# Sheet3.net
KiCad netlist of a schematic drawn in Altium Designer
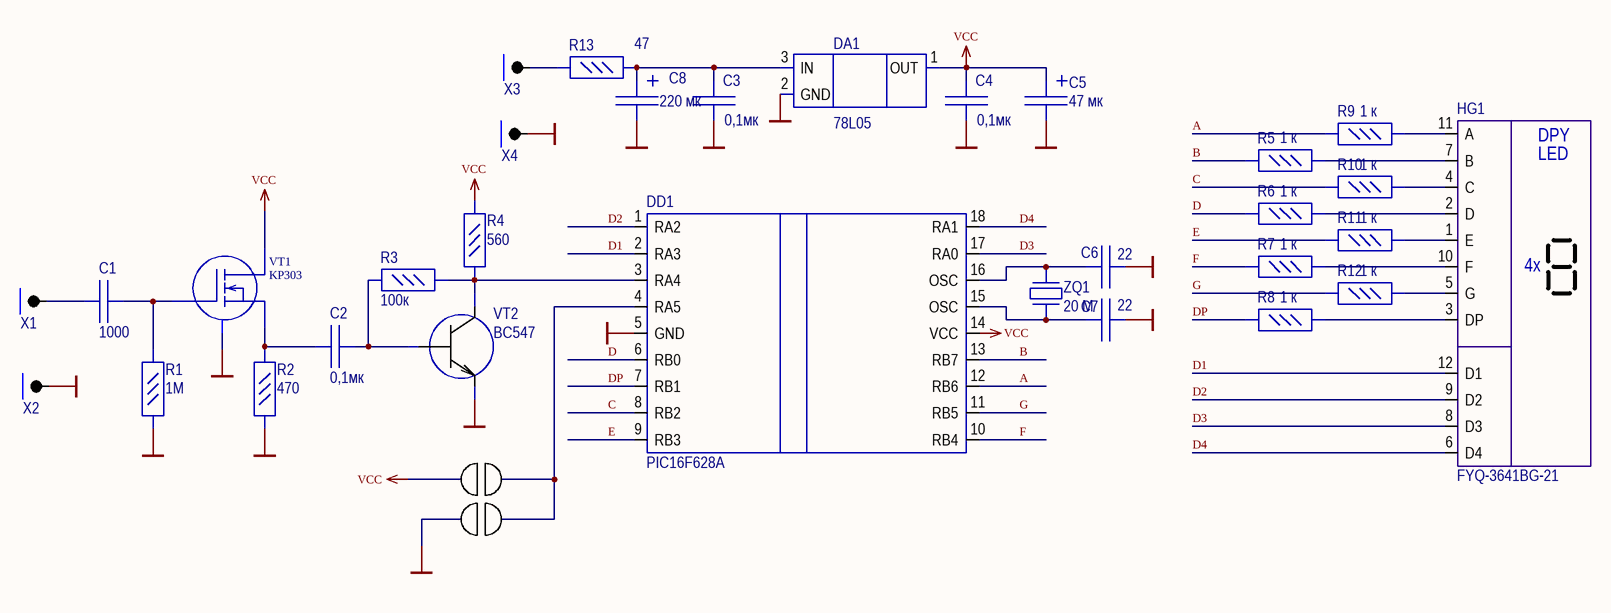
[diagram p0: Sheet3.SchDoc]

(export (version "E")
  (design (tool "Eeschema 10.0.6"))
  (components
    (comp (ref "C1") (value "1000") (footprint "К10-17Б") (libsource (lib "1. Passive") (part "C_К10-17Б")))
    (comp (ref "C2") (value "0,1мк") (footprint "К10-17Б") (libsource (lib "1. Passive") (part "C_К10-17Б")))
    (comp (ref "C3") (value "0,1мк") (footprint "К10-17Б") (libsource (lib "1. Passive") (part "C_К10-17Б")))
    (comp (ref "C4") (value "0,1мк") (footprint "К10-17Б") (libsource (lib "1. Passive") (part "C_К10-17Б")))
    (comp (ref "C5") (value "47 мк") (footprint "К50-35") (libsource (lib "1. Passive") (part "K50-35")))
    (comp (ref "C6") (value "22") (footprint "К10-17Б") (libsource (lib "1. Passive") (part "C_К10-17Б")))
    (comp (ref "C7") (value "22") (footprint "К10-17Б") (libsource (lib "1. Passive") (part "C_К10-17Б")))
    (comp (ref "C8")
      (value "220 мк")
      (footprint "К50-35 - 8x11.5")
      (libsource (lib "1. Passive") (part "K50-35"))
    )
    (comp (ref "DA1") (value "78L05") (footprint "КТ-26") (libsource (lib "2. Chips") (part "78L06")))
    (comp (ref "DD1")
      (value "PIC16F628A")
      (footprint "DIP18")
      (fields
        (field (name "MANUFACTURER PART NUMBER") "TB6600HG(O)")
        (field (name "OCTOPART") "https://octopart.com/tb6600hg%28o%29-toshiba-24612481")
        (field (name "MANUFACTURER") "Toshiba")
      )
      (libsource (lib "2. Chips") (part "PIC16F628A"))
    )
    (comp (ref "HG1")
      (value "FYQ-3641BG-21")
      (footprint "FYQ-3641")
      (description "4-х разр. светод. индикатор, зеленый, (ОА)")
      (libsource (lib "8. Other") (part "FYQ-3641BG-21"))
    )
    (comp (ref "R1") (value "1М") (footprint "R_C1-4_V") (libsource (lib "1. Passive") (part "R_C1-4")))
    (comp (ref "R2") (value "470") (footprint "R_C1-4_V") (libsource (lib "1. Passive") (part "R_C1-4")))
    (comp (ref "R3") (value "100к") (footprint "R_C1-4_V") (libsource (lib "1. Passive") (part "R_C1-4")))
    (comp (ref "R4") (value "560") (footprint "R_C1-4_V") (libsource (lib "1. Passive") (part "R_C1-4")))
    (comp (ref "R5") (value "1 к") (footprint "R_C1-4_V") (libsource (lib "1. Passive") (part "R_C1-4")))
    (comp (ref "R6") (value "1 к") (footprint "R_C1-4_V") (libsource (lib "1. Passive") (part "R_C1-4")))
    (comp (ref "R7") (value "1 к") (footprint "R_C1-4_V") (libsource (lib "1. Passive") (part "R_C1-4")))
    (comp (ref "R8") (value "1 к") (footprint "R_C1-4_V") (libsource (lib "1. Passive") (part "R_C1-4")))
    (comp (ref "R9") (value "1 к") (footprint "R_C1-4_V") (libsource (lib "1. Passive") (part "R_C1-4")))
    (comp (ref "R10") (value "1 к") (footprint "R_C1-4_V") (libsource (lib "1. Passive") (part "R_C1-4")))
    (comp (ref "R11") (value "1 к") (footprint "R_C1-4_V") (libsource (lib "1. Passive") (part "R_C1-4")))
    (comp (ref "R12") (value "1 к") (footprint "R_C1-4_V") (libsource (lib "1. Passive") (part "R_C1-4")))
    (comp (ref "R13") (value "47") (footprint "R_C1-4_V") (libsource (lib "1. Passive") (part "R_C1-4")))
    (comp (ref "VT1") (value "KP303") (footprint "KP303") (libsource (lib "KP303") (part "KP303")))
    (comp (ref "VT2") (value "BC547") (footprint "КТ-26") (libsource (lib "4. Transistors") (part "BC547")))
    (comp (ref "X1") (value "КТ") (footprint "KT") (libsource (lib "7. Connectors") (part "КТ")))
    (comp (ref "X2") (value "КТ") (footprint "KT") (libsource (lib "7. Connectors") (part "КТ")))
    (comp (ref "X3") (value "КТ") (footprint "KT") (libsource (lib "7. Connectors") (part "КТ")))
    (comp (ref "X4") (value "КТ") (footprint "KT") (libsource (lib "7. Connectors") (part "КТ")))
    (comp (ref "X5")
      (value "Solder_jumper")
      (footprint "Solder_jumper")
      (libsource (lib "11.Other") (part "Solder_jumper"))
    )
    (comp (ref "X6")
      (value "Solder_jumper")
      (footprint "Solder_jumper")
      (libsource (lib "11.Other") (part "Solder_jumper"))
    )
    (comp (ref "ZQ1") (value "20 M") (footprint "HC-49") (libsource (lib "5. Resonarors") (part "HC-49")))
  )
  (nets
    (net (code "1") (name "/A") (class "Default")
      (node (ref "DD1") (pin "12") (pinfunction "RB6_12") (pintype "passive"))
      (node (ref "R9") (pin "2") (pinfunction "2_2") (pintype "passive"))
    )
    (net (code "2") (name "/B") (class "Default")
      (node (ref "DD1") (pin "13") (pinfunction "RB7_13") (pintype "passive"))
      (node (ref "R5") (pin "2") (pinfunction "2_2") (pintype "passive"))
    )
    (net (code "3") (name "/C") (class "Default")
      (node (ref "DD1") (pin "8") (pinfunction "RB2_8") (pintype "passive"))
      (node (ref "R10") (pin "2") (pinfunction "2_2") (pintype "passive"))
    )
    (net (code "4") (name "/D") (class "Default")
      (node (ref "DD1") (pin "6") (pinfunction "RB0_6") (pintype "passive"))
      (node (ref "R6") (pin "2") (pinfunction "2_2") (pintype "passive"))
    )
    (net (code "5") (name "/D1") (class "Default")
      (node (ref "DD1") (pin "2") (pinfunction "RA3_2") (pintype "passive"))
      (node (ref "HG1") (pin "12") (pinfunction "D1_12") (pintype "passive"))
    )
    (net (code "6") (name "/D2") (class "Default")
      (node (ref "DD1") (pin "1") (pinfunction "RA2_1") (pintype "passive"))
      (node (ref "HG1") (pin "9") (pinfunction "D2_9") (pintype "passive"))
    )
    (net (code "7") (name "/D3") (class "Default")
      (node (ref "DD1") (pin "17") (pinfunction "RA0_17") (pintype "passive"))
      (node (ref "HG1") (pin "8") (pinfunction "D3_8") (pintype "passive"))
    )
    (net (code "8") (name "/D4") (class "Default")
      (node (ref "DD1") (pin "18") (pinfunction "RA1_18") (pintype "passive"))
      (node (ref "HG1") (pin "6") (pinfunction "D4_6") (pintype "passive"))
    )
    (net (code "9") (name "/DP") (class "Default")
      (node (ref "DD1") (pin "7") (pinfunction "RB1_7") (pintype "passive"))
      (node (ref "R8") (pin "2") (pinfunction "2_2") (pintype "passive"))
    )
    (net (code "10") (name "/E") (class "Default")
      (node (ref "DD1") (pin "9") (pinfunction "RB3_9") (pintype "passive"))
      (node (ref "R11") (pin "2") (pinfunction "2_2") (pintype "passive"))
    )
    (net (code "11") (name "/F") (class "Default")
      (node (ref "DD1") (pin "10") (pinfunction "RB4_10") (pintype "passive"))
      (node (ref "R7") (pin "2") (pinfunction "2_2") (pintype "passive"))
    )
    (net (code "12") (name "/G") (class "Default")
      (node (ref "DD1") (pin "11") (pinfunction "RB5_11") (pintype "passive"))
      (node (ref "R12") (pin "2") (pinfunction "2_2") (pintype "passive"))
    )
    (net (code "13") (name "GND") (class "Default")
      (node (ref "C3") (pin "1") (pinfunction "1_1") (pintype "passive"))
      (node (ref "C4") (pin "1") (pinfunction "1_1") (pintype "passive"))
      (node (ref "C5") (pin "2") (pinfunction "2_2") (pintype "passive"))
      (node (ref "C6") (pin "2") (pinfunction "2_2") (pintype "passive"))
      (node (ref "C7") (pin "2") (pinfunction "2_2") (pintype "passive"))
      (node (ref "C8") (pin "2") (pinfunction "2_2") (pintype "passive"))
      (node (ref "DA1") (pin "2") (pinfunction "GND_2") (pintype "passive"))
      (node (ref "DD1") (pin "5") (pinfunction "GND_5") (pintype "passive"))
      (node (ref "R1") (pin "1") (pinfunction "1_1") (pintype "passive"))
      (node (ref "R2") (pin "1") (pinfunction "1_1") (pintype "passive"))
      (node (ref "VT1") (pin "3") (pinfunction "5_3") (pintype "passive"))
      (node (ref "VT2") (pin "3") (pinfunction "E_3") (pintype "passive"))
      (node (ref "X2") (pin "1") (pinfunction "1_1") (pintype "passive"))
      (node (ref "X4") (pin "1") (pinfunction "1_1") (pintype "passive"))
      (node (ref "X6") (pin "1") (pinfunction "1_1") (pintype "passive"))
    )
    (net (code "14") (name "Net-(C1-Pad2)") (class "Default")
      (node (ref "C1") (pin "2") (pinfunction "2_2") (pintype "passive"))
      (node (ref "X1") (pin "1") (pinfunction "1_1") (pintype "passive"))
    )
    (net (code "15") (name "Net-(C6-Pad1)") (class "Default")
      (node (ref "C6") (pin "1") (pinfunction "1_1") (pintype "passive"))
      (node (ref "DD1") (pin "16") (pinfunction "OSC_16") (pintype "passive"))
      (node (ref "ZQ1") (pin "1") (pinfunction "1_1") (pintype "passive"))
    )
    (net (code "16") (name "Net-(C7-Pad1)") (class "Default")
      (node (ref "C7") (pin "1") (pinfunction "1_1") (pintype "passive"))
      (node (ref "DD1") (pin "15") (pinfunction "OSC_15") (pintype "passive"))
      (node (ref "ZQ1") (pin "2") (pinfunction "2_2") (pintype "passive"))
    )
    (net (code "17") (name "Net-(DA1-IN)") (class "Default")
      (node (ref "C3") (pin "2") (pinfunction "2_2") (pintype "passive"))
      (node (ref "C8") (pin "1") (pinfunction "1_1") (pintype "passive"))
      (node (ref "DA1") (pin "3") (pinfunction "IN_3") (pintype "passive"))
      (node (ref "R13") (pin "1") (pinfunction "1_1") (pintype "passive"))
    )
    (net (code "18") (name "Net-(DD1-RA4)") (class "Default")
      (node (ref "DD1") (pin "3") (pinfunction "RA4_3") (pintype "passive"))
      (node (ref "R3") (pin "2") (pinfunction "2_2") (pintype "passive"))
      (node (ref "R4") (pin "2") (pinfunction "2_2") (pintype "passive"))
      (node (ref "VT2") (pin "1") (pinfunction "C_1") (pintype "passive"))
    )
    (net (code "19") (name "Net-(DD1-RA5)") (class "Default")
      (node (ref "DD1") (pin "4") (pinfunction "RA5_4") (pintype "passive"))
      (node (ref "X5") (pin "2") (pinfunction "2_2") (pintype "passive"))
      (node (ref "X6") (pin "2") (pinfunction "2_2") (pintype "passive"))
    )
    (net (code "20") (name "Net-(HG1-A)") (class "Default")
      (node (ref "HG1") (pin "11") (pinfunction "A_11") (pintype "passive"))
      (node (ref "R9") (pin "1") (pinfunction "1_1") (pintype "passive"))
    )
    (net (code "21") (name "Net-(HG1-B)") (class "Default")
      (node (ref "HG1") (pin "7") (pinfunction "B_7") (pintype "passive"))
      (node (ref "R5") (pin "1") (pinfunction "1_1") (pintype "passive"))
    )
    (net (code "22") (name "Net-(HG1-C)") (class "Default")
      (node (ref "HG1") (pin "4") (pinfunction "C_4") (pintype "passive"))
      (node (ref "R10") (pin "1") (pinfunction "1_1") (pintype "passive"))
    )
    (net (code "23") (name "Net-(HG1-D)") (class "Default")
      (node (ref "HG1") (pin "2") (pinfunction "D_2") (pintype "passive"))
      (node (ref "R6") (pin "1") (pinfunction "1_1") (pintype "passive"))
    )
    (net (code "24") (name "Net-(HG1-DP)") (class "Default")
      (node (ref "HG1") (pin "3") (pinfunction "DP_3") (pintype "passive"))
      (node (ref "R8") (pin "1") (pinfunction "1_1") (pintype "passive"))
    )
    (net (code "25") (name "Net-(HG1-E)") (class "Default")
      (node (ref "HG1") (pin "1") (pinfunction "E_1") (pintype "passive"))
      (node (ref "R11") (pin "1") (pinfunction "1_1") (pintype "passive"))
    )
    (net (code "26") (name "Net-(HG1-F)") (class "Default")
      (node (ref "HG1") (pin "10") (pinfunction "F_10") (pintype "passive"))
      (node (ref "R7") (pin "1") (pinfunction "1_1") (pintype "passive"))
    )
    (net (code "27") (name "Net-(HG1-G)") (class "Default")
      (node (ref "HG1") (pin "5") (pinfunction "G_5") (pintype "passive"))
      (node (ref "R12") (pin "1") (pinfunction "1_1") (pintype "passive"))
    )
    (net (code "28") (name "Net-(R13-Pad2)") (class "Default")
      (node (ref "R13") (pin "2") (pinfunction "2_2") (pintype "passive"))
      (node (ref "X3") (pin "1") (pinfunction "1_1") (pintype "passive"))
    )
    (net (code "29") (name "Net-(VT1-G)") (class "Default")
      (node (ref "C1") (pin "1") (pinfunction "1_1") (pintype "passive"))
      (node (ref "R1") (pin "2") (pinfunction "2_2") (pintype "passive"))
      (node (ref "VT1") (pin "1") (pinfunction "G_1") (pintype "passive"))
    )
    (net (code "30") (name "Net-(VT1-S)") (class "Default")
      (node (ref "C2") (pin "2") (pinfunction "2_2") (pintype "passive"))
      (node (ref "R2") (pin "2") (pinfunction "2_2") (pintype "passive"))
      (node (ref "VT1") (pin "2") (pinfunction "S_2") (pintype "passive"))
    )
    (net (code "31") (name "Net-(VT2-B)") (class "Default")
      (node (ref "C2") (pin "1") (pinfunction "1_1") (pintype "passive"))
      (node (ref "R3") (pin "1") (pinfunction "1_1") (pintype "passive"))
      (node (ref "VT2") (pin "2") (pinfunction "B_2") (pintype "passive"))
    )
    (net (code "32") (name "VCC") (class "Default")
      (node (ref "C4") (pin "2") (pinfunction "2_2") (pintype "passive"))
      (node (ref "C5") (pin "1") (pinfunction "1_1") (pintype "passive"))
      (node (ref "DA1") (pin "1") (pinfunction "OUT_1") (pintype "passive"))
      (node (ref "DD1") (pin "14") (pinfunction "VCC_14") (pintype "passive"))
      (node (ref "R4") (pin "1") (pinfunction "1_1") (pintype "passive"))
      (node (ref "VT1") (pin "4") (pinfunction "D_4") (pintype "passive"))
      (node (ref "X5") (pin "1") (pinfunction "1_1") (pintype "passive"))
    )
  )
)
